# tinyclock.net
KiCad netlist of a schematic drawn in EAGLE
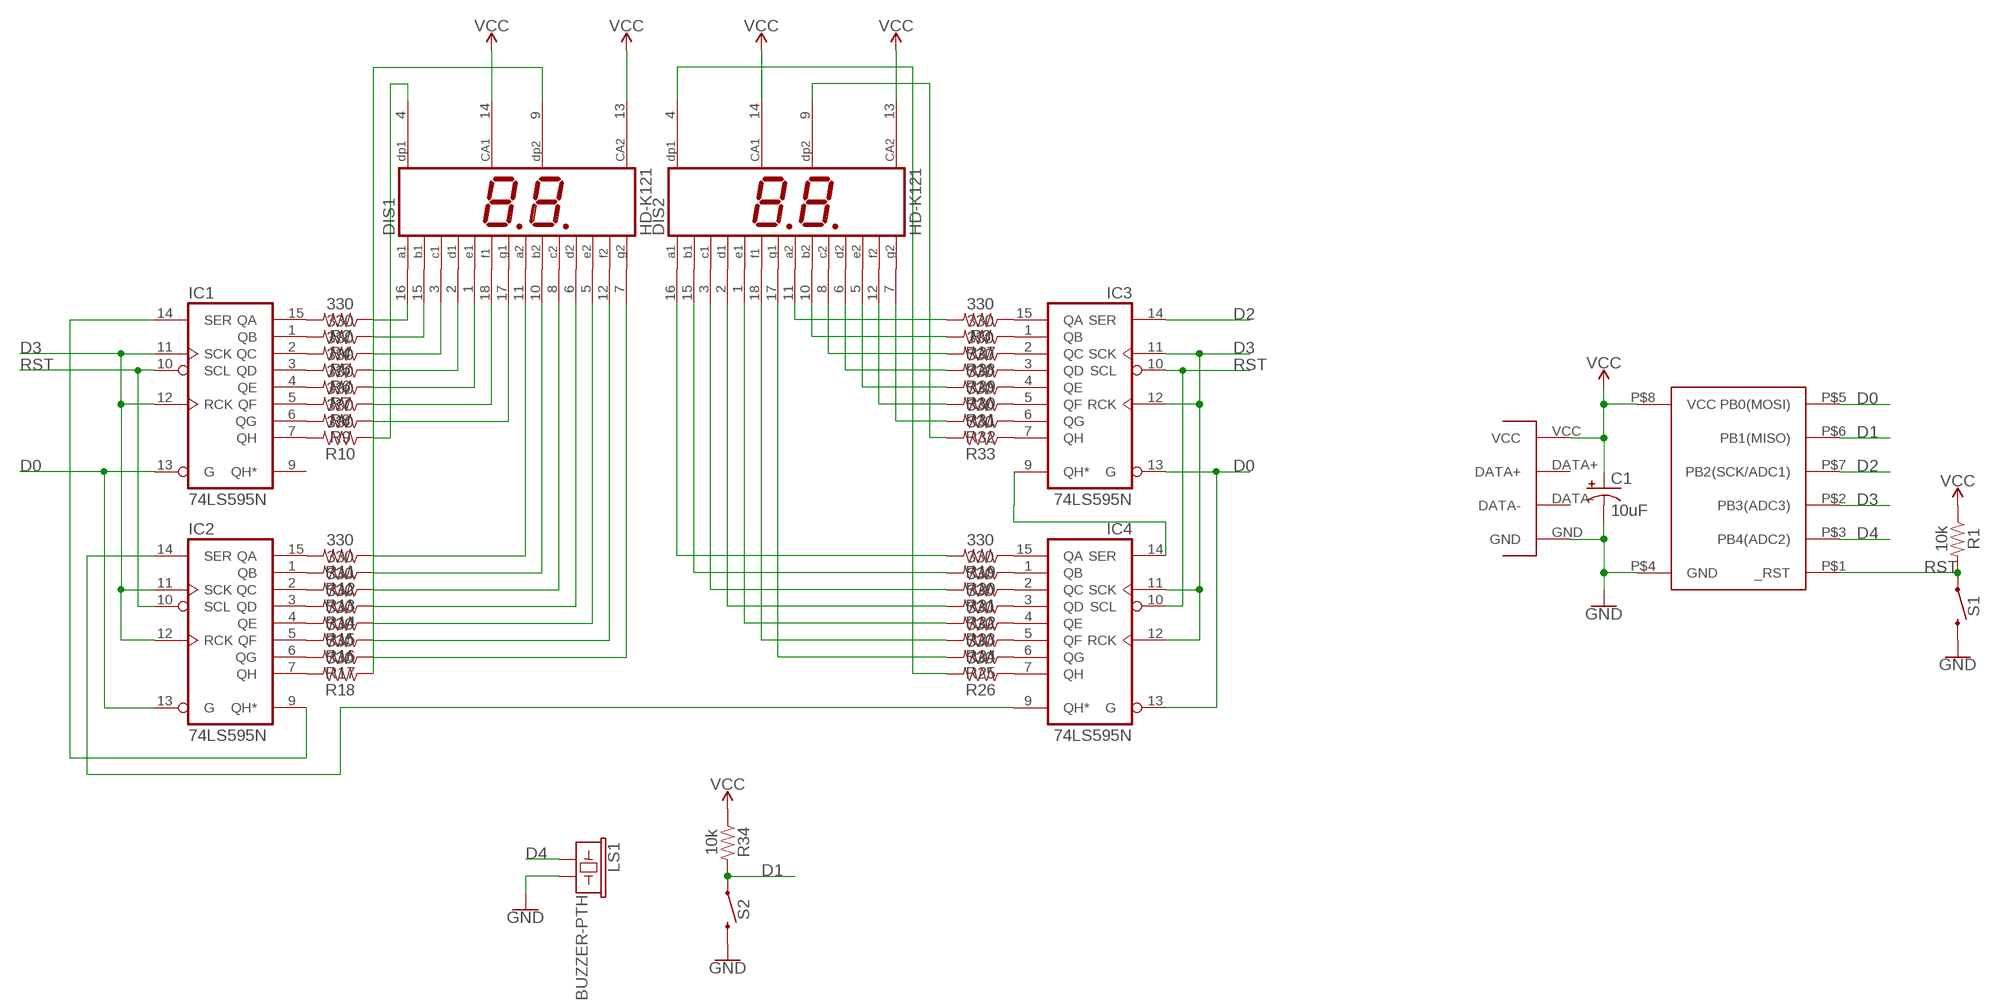
[diagram p0: schematic, sheet 1]

(export (version "E")
  (design (tool "Eeschema 10.0.6"))
  (components
    (comp (ref "C1")
      (value "10uF")
      (footprint "eagle-import:CPOL-RADIAL-5MM-10MM")
      (libsource (lib "eagle-import") (part "1000UF-RADIAL-5MM-25V-20%"))
    )
    (comp (ref "DIS1")
      (value "HD-K121")
      (footprint "eagle-import:HDSP-R")
      (libsource (lib "eagle-import") (part "HD-K121"))
    )
    (comp (ref "DIS2")
      (value "HD-K121")
      (footprint "eagle-import:HDSP-R")
      (libsource (lib "eagle-import") (part "HD-K121"))
    )
    (comp (ref "IC1")
      (value "74LS595N")
      (footprint "eagle-import:DIL16")
      (libsource (lib "eagle-import") (part "74595NLS"))
    )
    (comp (ref "IC2")
      (value "74LS595N")
      (footprint "eagle-import:DIL16")
      (libsource (lib "eagle-import") (part "74595NLS"))
    )
    (comp (ref "IC3")
      (value "74LS595N")
      (footprint "eagle-import:DIL16")
      (libsource (lib "eagle-import") (part "74595NLS"))
    )
    (comp (ref "IC4")
      (value "74LS595N")
      (footprint "eagle-import:DIL16")
      (libsource (lib "eagle-import") (part "74595NLS"))
    )
    (comp (ref "LS1")
      (value "BUZZER-PTH")
      (footprint "eagle-import:BUZZER-12MM")
      (libsource (lib "eagle-import") (part "BUZZER-PTH"))
    )
    (comp (ref "R1")
      (value "10k")
      (footprint "eagle-import:AXIAL-0.1")
      (libsource (lib "eagle-import") (part "1KOHM-VERT-1/4W-5%"))
    )
    (comp (ref "R2")
      (value "330")
      (footprint "eagle-import:AXIAL-0.1")
      (libsource (lib "eagle-import") (part "1KOHM-VERT-1/4W-5%"))
    )
    (comp (ref "R3")
      (value "330")
      (footprint "eagle-import:AXIAL-0.1")
      (libsource (lib "eagle-import") (part "1KOHM-VERT-1/4W-5%"))
    )
    (comp (ref "R4")
      (value "330")
      (footprint "eagle-import:AXIAL-0.1")
      (libsource (lib "eagle-import") (part "1KOHM-VERT-1/4W-5%"))
    )
    (comp (ref "R5")
      (value "330")
      (footprint "eagle-import:AXIAL-0.1")
      (libsource (lib "eagle-import") (part "1KOHM-VERT-1/4W-5%"))
    )
    (comp (ref "R6")
      (value "330")
      (footprint "eagle-import:AXIAL-0.1")
      (libsource (lib "eagle-import") (part "1KOHM-VERT-1/4W-5%"))
    )
    (comp (ref "R7")
      (value "330")
      (footprint "eagle-import:AXIAL-0.1")
      (libsource (lib "eagle-import") (part "1KOHM-VERT-1/4W-5%"))
    )
    (comp (ref "R8")
      (value "330")
      (footprint "eagle-import:AXIAL-0.1")
      (libsource (lib "eagle-import") (part "1KOHM-VERT-1/4W-5%"))
    )
    (comp (ref "R9")
      (value "330")
      (footprint "eagle-import:AXIAL-0.1")
      (libsource (lib "eagle-import") (part "1KOHM-VERT-1/4W-5%"))
    )
    (comp (ref "R10")
      (value "330")
      (footprint "eagle-import:AXIAL-0.1")
      (libsource (lib "eagle-import") (part "1KOHM-VERT-1/4W-5%"))
    )
    (comp (ref "R11")
      (value "330")
      (footprint "eagle-import:AXIAL-0.1")
      (libsource (lib "eagle-import") (part "1KOHM-VERT-1/4W-5%"))
    )
    (comp (ref "R12")
      (value "330")
      (footprint "eagle-import:AXIAL-0.1")
      (libsource (lib "eagle-import") (part "1KOHM-VERT-1/4W-5%"))
    )
    (comp (ref "R13")
      (value "330")
      (footprint "eagle-import:AXIAL-0.1")
      (libsource (lib "eagle-import") (part "1KOHM-VERT-1/4W-5%"))
    )
    (comp (ref "R14")
      (value "330")
      (footprint "eagle-import:AXIAL-0.1")
      (libsource (lib "eagle-import") (part "1KOHM-VERT-1/4W-5%"))
    )
    (comp (ref "R15")
      (value "330")
      (footprint "eagle-import:AXIAL-0.1")
      (libsource (lib "eagle-import") (part "1KOHM-VERT-1/4W-5%"))
    )
    (comp (ref "R16")
      (value "330")
      (footprint "eagle-import:AXIAL-0.1")
      (libsource (lib "eagle-import") (part "1KOHM-VERT-1/4W-5%"))
    )
    (comp (ref "R17")
      (value "330")
      (footprint "eagle-import:AXIAL-0.1")
      (libsource (lib "eagle-import") (part "1KOHM-VERT-1/4W-5%"))
    )
    (comp (ref "R18")
      (value "330")
      (footprint "eagle-import:AXIAL-0.1")
      (libsource (lib "eagle-import") (part "1KOHM-VERT-1/4W-5%"))
    )
    (comp (ref "R19")
      (value "330")
      (footprint "eagle-import:AXIAL-0.1")
      (libsource (lib "eagle-import") (part "1KOHM-VERT-1/4W-5%"))
    )
    (comp (ref "R20")
      (value "330")
      (footprint "eagle-import:AXIAL-0.1")
      (libsource (lib "eagle-import") (part "1KOHM-VERT-1/4W-5%"))
    )
    (comp (ref "R21")
      (value "330")
      (footprint "eagle-import:AXIAL-0.1")
      (libsource (lib "eagle-import") (part "1KOHM-VERT-1/4W-5%"))
    )
    (comp (ref "R22")
      (value "330")
      (footprint "eagle-import:AXIAL-0.1")
      (libsource (lib "eagle-import") (part "1KOHM-VERT-1/4W-5%"))
    )
    (comp (ref "R23")
      (value "330")
      (footprint "eagle-import:AXIAL-0.1")
      (libsource (lib "eagle-import") (part "1KOHM-VERT-1/4W-5%"))
    )
    (comp (ref "R24")
      (value "330")
      (footprint "eagle-import:AXIAL-0.1")
      (libsource (lib "eagle-import") (part "1KOHM-VERT-1/4W-5%"))
    )
    (comp (ref "R25")
      (value "330")
      (footprint "eagle-import:AXIAL-0.1")
      (libsource (lib "eagle-import") (part "1KOHM-VERT-1/4W-5%"))
    )
    (comp (ref "R26")
      (value "330")
      (footprint "eagle-import:AXIAL-0.1")
      (libsource (lib "eagle-import") (part "1KOHM-VERT-1/4W-5%"))
    )
    (comp (ref "R27")
      (value "330")
      (footprint "eagle-import:AXIAL-0.1")
      (libsource (lib "eagle-import") (part "1KOHM-VERT-1/4W-5%"))
    )
    (comp (ref "R28")
      (value "330")
      (footprint "eagle-import:AXIAL-0.1")
      (libsource (lib "eagle-import") (part "1KOHM-VERT-1/4W-5%"))
    )
    (comp (ref "R29")
      (value "330")
      (footprint "eagle-import:AXIAL-0.1")
      (libsource (lib "eagle-import") (part "1KOHM-VERT-1/4W-5%"))
    )
    (comp (ref "R30")
      (value "330")
      (footprint "eagle-import:AXIAL-0.1")
      (libsource (lib "eagle-import") (part "1KOHM-VERT-1/4W-5%"))
    )
    (comp (ref "R31")
      (value "330")
      (footprint "eagle-import:AXIAL-0.1")
      (libsource (lib "eagle-import") (part "1KOHM-VERT-1/4W-5%"))
    )
    (comp (ref "R32")
      (value "330")
      (footprint "eagle-import:AXIAL-0.1")
      (libsource (lib "eagle-import") (part "1KOHM-VERT-1/4W-5%"))
    )
    (comp (ref "R33")
      (value "330")
      (footprint "eagle-import:AXIAL-0.1")
      (libsource (lib "eagle-import") (part "1KOHM-VERT-1/4W-5%"))
    )
    (comp (ref "R34")
      (value "10k")
      (footprint "eagle-import:AXIAL-0.1")
      (libsource (lib "eagle-import") (part "1KOHM-VERT-1/4W-5%"))
    )
    (comp (ref "S1")
      (value "MOMENTARY-SWITCH-SPST-PTH-6.0MM")
      (footprint "eagle-import:TACTILE_SWITCH_PTH_6.0MM")
      (libsource (lib "eagle-import") (part "MOMENTARY-SWITCH-SPST-PTH-6.0MM"))
    )
    (comp (ref "S2")
      (value "MOMENTARY-SWITCH-SPST-PTH-6.0MM")
      (footprint "eagle-import:TACTILE_SWITCH_PTH_6.0MM")
      (libsource (lib "eagle-import") (part "MOMENTARY-SWITCH-SPST-PTH-6.0MM"))
    )
    (comp (ref "U$1")
      (value "ATTINY85-DIP8")
      (footprint "eagle-import:DIP8")
      (libsource (lib "eagle-import") (part "ATTINY85-DIP8"))
    )
    (comp (ref "U$2")
      (value "USBPCB")
      (footprint "eagle-import:USBPCB")
      (libsource (lib "eagle-import") (part "USBPCB"))
    )
  )
  (nets
    (net (code "1") (name "/D0") (class "Default")
      (node (ref "IC1") (pin "13") (pinfunction "G_13") (pintype "input"))
      (node (ref "IC2") (pin "13") (pinfunction "G_13") (pintype "input"))
      (node (ref "IC3") (pin "13") (pinfunction "G_13") (pintype "input"))
      (node (ref "IC4") (pin "13") (pinfunction "G_13") (pintype "input"))
      (node (ref "U$1") (pin "P$5") (pinfunction "PB0(MOSI)_P$5") (pintype "bidirectional"))
    )
    (net (code "2") (name "/D1") (class "Default")
      (node (ref "R34") (pin "P$2") (pinfunction "2_P$2") (pintype "passive"))
      (node (ref "S2") (pin "1") (pinfunction "1_1") (pintype "passive"))
      (node (ref "U$1") (pin "P$6") (pinfunction "PB1(MISO)_P$6") (pintype "bidirectional"))
    )
    (net (code "3") (name "/D2") (class "Default")
      (node (ref "IC3") (pin "14") (pinfunction "SER_14") (pintype "input"))
      (node (ref "U$1") (pin "P$7") (pinfunction "PB2(SCK/ADC1)_P$7") (pintype "bidirectional"))
    )
    (net (code "4") (name "/D3") (class "Default")
      (node (ref "IC1") (pin "11") (pinfunction "SCK_11") (pintype "input"))
      (node (ref "IC1") (pin "12") (pinfunction "RCK_12") (pintype "input"))
      (node (ref "IC2") (pin "11") (pinfunction "SCK_11") (pintype "input"))
      (node (ref "IC2") (pin "12") (pinfunction "RCK_12") (pintype "input"))
      (node (ref "IC3") (pin "11") (pinfunction "SCK_11") (pintype "input"))
      (node (ref "IC3") (pin "12") (pinfunction "RCK_12") (pintype "input"))
      (node (ref "IC4") (pin "11") (pinfunction "SCK_11") (pintype "input"))
      (node (ref "IC4") (pin "12") (pinfunction "RCK_12") (pintype "input"))
      (node (ref "U$1") (pin "P$2") (pinfunction "PB3(ADC3)_P$2") (pintype "bidirectional"))
    )
    (net (code "5") (name "/D4") (class "Default")
      (node (ref "LS1") (pin "+") (pinfunction "1_+") (pintype "passive"))
      (node (ref "U$1") (pin "P$3") (pinfunction "PB4(ADC2)_P$3") (pintype "bidirectional"))
    )
    (net (code "6") (name "/RST") (class "Default")
      (node (ref "IC1") (pin "10") (pinfunction "SCL_10") (pintype "input"))
      (node (ref "IC2") (pin "10") (pinfunction "SCL_10") (pintype "input"))
      (node (ref "IC3") (pin "10") (pinfunction "SCL_10") (pintype "input"))
      (node (ref "IC4") (pin "10") (pinfunction "SCL_10") (pintype "input"))
      (node (ref "R1") (pin "P$2") (pinfunction "2_P$2") (pintype "passive"))
      (node (ref "S1") (pin "1") (pinfunction "1_1") (pintype "passive"))
      (node (ref "U$1") (pin "P$1") (pinfunction "_RST_P$1") (pintype "bidirectional"))
    )
    (net (code "7") (name "GND") (class "Default")
      (node (ref "C1") (pin "-") (pinfunction "-_-") (pintype "passive"))
      (node (ref "LS1") (pin "-") (pinfunction "2_-") (pintype "passive"))
      (node (ref "S1") (pin "3") (pinfunction "2_3") (pintype "passive"))
      (node (ref "S2") (pin "3") (pinfunction "2_3") (pintype "passive"))
      (node (ref "U$1") (pin "P$4") (pinfunction "GND_P$4") (pintype "bidirectional"))
      (node (ref "U$2") (pin "GND") (pinfunction "GND_GND") (pintype "bidirectional"))
    )
    (net (code "8") (name "Net-(DIS1-A1)") (class "Default")
      (node (ref "DIS1") (pin "16") (pinfunction "A1_16") (pintype "passive"))
      (node (ref "R2") (pin "P$1") (pinfunction "1_P$1") (pintype "passive"))
    )
    (net (code "9") (name "Net-(DIS1-A2)") (class "Default")
      (node (ref "DIS1") (pin "11") (pinfunction "A2_11") (pintype "passive"))
      (node (ref "R11") (pin "P$1") (pinfunction "1_P$1") (pintype "passive"))
    )
    (net (code "10") (name "Net-(DIS1-B1)") (class "Default")
      (node (ref "DIS1") (pin "15") (pinfunction "B1_15") (pintype "passive"))
      (node (ref "R4") (pin "P$1") (pinfunction "1_P$1") (pintype "passive"))
    )
    (net (code "11") (name "Net-(DIS1-B2)") (class "Default")
      (node (ref "DIS1") (pin "10") (pinfunction "B2_10") (pintype "passive"))
      (node (ref "R12") (pin "P$1") (pinfunction "1_P$1") (pintype "passive"))
    )
    (net (code "12") (name "Net-(DIS1-C1)") (class "Default")
      (node (ref "DIS1") (pin "3") (pinfunction "C1_3") (pintype "passive"))
      (node (ref "R5") (pin "P$1") (pinfunction "1_P$1") (pintype "passive"))
    )
    (net (code "13") (name "Net-(DIS1-C2)") (class "Default")
      (node (ref "DIS1") (pin "8") (pinfunction "C2_8") (pintype "passive"))
      (node (ref "R13") (pin "P$1") (pinfunction "1_P$1") (pintype "passive"))
    )
    (net (code "14") (name "Net-(DIS1-D1)") (class "Default")
      (node (ref "DIS1") (pin "2") (pinfunction "D1_2") (pintype "passive"))
      (node (ref "R6") (pin "P$1") (pinfunction "1_P$1") (pintype "passive"))
    )
    (net (code "15") (name "Net-(DIS1-D2)") (class "Default")
      (node (ref "DIS1") (pin "6") (pinfunction "D2_6") (pintype "passive"))
      (node (ref "R14") (pin "P$1") (pinfunction "1_P$1") (pintype "passive"))
    )
    (net (code "16") (name "Net-(DIS1-DP1)") (class "Default")
      (node (ref "DIS1") (pin "4") (pinfunction "DP1_4") (pintype "passive"))
      (node (ref "R10") (pin "P$1") (pinfunction "1_P$1") (pintype "passive"))
    )
    (net (code "17") (name "Net-(DIS1-DP2)") (class "Default")
      (node (ref "DIS1") (pin "9") (pinfunction "DP2_9") (pintype "passive"))
      (node (ref "R18") (pin "P$1") (pinfunction "1_P$1") (pintype "passive"))
    )
    (net (code "18") (name "Net-(DIS1-E1)") (class "Default")
      (node (ref "DIS1") (pin "1") (pinfunction "E1_1") (pintype "passive"))
      (node (ref "R7") (pin "P$1") (pinfunction "1_P$1") (pintype "passive"))
    )
    (net (code "19") (name "Net-(DIS1-E2)") (class "Default")
      (node (ref "DIS1") (pin "5") (pinfunction "E2_5") (pintype "passive"))
      (node (ref "R15") (pin "P$1") (pinfunction "1_P$1") (pintype "passive"))
    )
    (net (code "20") (name "Net-(DIS1-F1)") (class "Default")
      (node (ref "DIS1") (pin "18") (pinfunction "F1_18") (pintype "passive"))
      (node (ref "R8") (pin "P$1") (pinfunction "1_P$1") (pintype "passive"))
    )
    (net (code "21") (name "Net-(DIS1-F2)") (class "Default")
      (node (ref "DIS1") (pin "12") (pinfunction "F2_12") (pintype "passive"))
      (node (ref "R16") (pin "P$1") (pinfunction "1_P$1") (pintype "passive"))
    )
    (net (code "22") (name "Net-(DIS1-G1)") (class "Default")
      (node (ref "DIS1") (pin "17") (pinfunction "G1_17") (pintype "passive"))
      (node (ref "R9") (pin "P$1") (pinfunction "1_P$1") (pintype "passive"))
    )
    (net (code "23") (name "Net-(DIS1-G2)") (class "Default")
      (node (ref "DIS1") (pin "7") (pinfunction "G2_7") (pintype "passive"))
      (node (ref "R17") (pin "P$1") (pinfunction "1_P$1") (pintype "passive"))
    )
    (net (code "24") (name "Net-(DIS2-A1)") (class "Default")
      (node (ref "DIS2") (pin "16") (pinfunction "A1_16") (pintype "passive"))
      (node (ref "R19") (pin "P$2") (pinfunction "2_P$2") (pintype "passive"))
    )
    (net (code "25") (name "Net-(DIS2-A2)") (class "Default")
      (node (ref "DIS2") (pin "11") (pinfunction "A2_11") (pintype "passive"))
      (node (ref "R3") (pin "P$2") (pinfunction "2_P$2") (pintype "passive"))
    )
    (net (code "26") (name "Net-(DIS2-B1)") (class "Default")
      (node (ref "DIS2") (pin "15") (pinfunction "B1_15") (pintype "passive"))
      (node (ref "R20") (pin "P$2") (pinfunction "2_P$2") (pintype "passive"))
    )
    (net (code "27") (name "Net-(DIS2-B2)") (class "Default")
      (node (ref "DIS2") (pin "10") (pinfunction "B2_10") (pintype "passive"))
      (node (ref "R27") (pin "P$2") (pinfunction "2_P$2") (pintype "passive"))
    )
    (net (code "28") (name "Net-(DIS2-C1)") (class "Default")
      (node (ref "DIS2") (pin "3") (pinfunction "C1_3") (pintype "passive"))
      (node (ref "R21") (pin "P$2") (pinfunction "2_P$2") (pintype "passive"))
    )
    (net (code "29") (name "Net-(DIS2-C2)") (class "Default")
      (node (ref "DIS2") (pin "8") (pinfunction "C2_8") (pintype "passive"))
      (node (ref "R28") (pin "P$2") (pinfunction "2_P$2") (pintype "passive"))
    )
    (net (code "30") (name "Net-(DIS2-D1)") (class "Default")
      (node (ref "DIS2") (pin "2") (pinfunction "D1_2") (pintype "passive"))
      (node (ref "R22") (pin "P$2") (pinfunction "2_P$2") (pintype "passive"))
    )
    (net (code "31") (name "Net-(DIS2-D2)") (class "Default")
      (node (ref "DIS2") (pin "6") (pinfunction "D2_6") (pintype "passive"))
      (node (ref "R29") (pin "P$2") (pinfunction "2_P$2") (pintype "passive"))
    )
    (net (code "32") (name "Net-(DIS2-DP1)") (class "Default")
      (node (ref "DIS2") (pin "4") (pinfunction "DP1_4") (pintype "passive"))
      (node (ref "R26") (pin "P$2") (pinfunction "2_P$2") (pintype "passive"))
    )
    (net (code "33") (name "Net-(DIS2-DP2)") (class "Default")
      (node (ref "DIS2") (pin "9") (pinfunction "DP2_9") (pintype "passive"))
      (node (ref "R33") (pin "P$2") (pinfunction "2_P$2") (pintype "passive"))
    )
    (net (code "34") (name "Net-(DIS2-E1)") (class "Default")
      (node (ref "DIS2") (pin "1") (pinfunction "E1_1") (pintype "passive"))
      (node (ref "R23") (pin "P$2") (pinfunction "2_P$2") (pintype "passive"))
    )
    (net (code "35") (name "Net-(DIS2-E2)") (class "Default")
      (node (ref "DIS2") (pin "5") (pinfunction "E2_5") (pintype "passive"))
      (node (ref "R30") (pin "P$2") (pinfunction "2_P$2") (pintype "passive"))
    )
    (net (code "36") (name "Net-(DIS2-F1)") (class "Default")
      (node (ref "DIS2") (pin "18") (pinfunction "F1_18") (pintype "passive"))
      (node (ref "R24") (pin "P$2") (pinfunction "2_P$2") (pintype "passive"))
    )
    (net (code "37") (name "Net-(DIS2-F2)") (class "Default")
      (node (ref "DIS2") (pin "12") (pinfunction "F2_12") (pintype "passive"))
      (node (ref "R31") (pin "P$2") (pinfunction "2_P$2") (pintype "passive"))
    )
    (net (code "38") (name "Net-(DIS2-G1)") (class "Default")
      (node (ref "DIS2") (pin "17") (pinfunction "G1_17") (pintype "passive"))
      (node (ref "R25") (pin "P$2") (pinfunction "2_P$2") (pintype "passive"))
    )
    (net (code "39") (name "Net-(DIS2-G2)") (class "Default")
      (node (ref "DIS2") (pin "7") (pinfunction "G2_7") (pintype "passive"))
      (node (ref "R32") (pin "P$2") (pinfunction "2_P$2") (pintype "passive"))
    )
    (net (code "40") (name "Net-(IC1A-QA)") (class "Default")
      (node (ref "IC1") (pin "15") (pinfunction "QA_15") (pintype "tri_state"))
      (node (ref "R2") (pin "P$2") (pinfunction "2_P$2") (pintype "passive"))
    )
    (net (code "41") (name "Net-(IC1A-QB)") (class "Default")
      (node (ref "IC1") (pin "1") (pinfunction "QB_1") (pintype "tri_state"))
      (node (ref "R4") (pin "P$2") (pinfunction "2_P$2") (pintype "passive"))
    )
    (net (code "42") (name "Net-(IC1A-QC)") (class "Default")
      (node (ref "IC1") (pin "2") (pinfunction "QC_2") (pintype "tri_state"))
      (node (ref "R5") (pin "P$2") (pinfunction "2_P$2") (pintype "passive"))
    )
    (net (code "43") (name "Net-(IC1A-QD)") (class "Default")
      (node (ref "IC1") (pin "3") (pinfunction "QD_3") (pintype "tri_state"))
      (node (ref "R6") (pin "P$2") (pinfunction "2_P$2") (pintype "passive"))
    )
    (net (code "44") (name "Net-(IC1A-QE)") (class "Default")
      (node (ref "IC1") (pin "4") (pinfunction "QE_4") (pintype "tri_state"))
      (node (ref "R7") (pin "P$2") (pinfunction "2_P$2") (pintype "passive"))
    )
    (net (code "45") (name "Net-(IC1A-QF)") (class "Default")
      (node (ref "IC1") (pin "5") (pinfunction "QF_5") (pintype "tri_state"))
      (node (ref "R8") (pin "P$2") (pinfunction "2_P$2") (pintype "passive"))
    )
    (net (code "46") (name "Net-(IC1A-QG)") (class "Default")
      (node (ref "IC1") (pin "6") (pinfunction "QG_6") (pintype "tri_state"))
      (node (ref "R9") (pin "P$2") (pinfunction "2_P$2") (pintype "passive"))
    )
    (net (code "47") (name "Net-(IC1A-QH)") (class "Default")
      (node (ref "IC1") (pin "7") (pinfunction "QH_7") (pintype "tri_state"))
      (node (ref "R10") (pin "P$2") (pinfunction "2_P$2") (pintype "passive"))
    )
    (net (code "48") (name "Net-(IC1A-SER)") (class "Default")
      (node (ref "IC1") (pin "14") (pinfunction "SER_14") (pintype "input"))
      (node (ref "IC2") (pin "9") (pinfunction "QH*_9") (pintype "tri_state"))
    )
    (net (code "49") (name "Net-(IC2A-QA)") (class "Default")
      (node (ref "IC2") (pin "15") (pinfunction "QA_15") (pintype "tri_state"))
      (node (ref "R11") (pin "P$2") (pinfunction "2_P$2") (pintype "passive"))
    )
    (net (code "50") (name "Net-(IC2A-QB)") (class "Default")
      (node (ref "IC2") (pin "1") (pinfunction "QB_1") (pintype "tri_state"))
      (node (ref "R12") (pin "P$2") (pinfunction "2_P$2") (pintype "passive"))
    )
    (net (code "51") (name "Net-(IC2A-QC)") (class "Default")
      (node (ref "IC2") (pin "2") (pinfunction "QC_2") (pintype "tri_state"))
      (node (ref "R13") (pin "P$2") (pinfunction "2_P$2") (pintype "passive"))
    )
    (net (code "52") (name "Net-(IC2A-QD)") (class "Default")
      (node (ref "IC2") (pin "3") (pinfunction "QD_3") (pintype "tri_state"))
      (node (ref "R14") (pin "P$2") (pinfunction "2_P$2") (pintype "passive"))
    )
    (net (code "53") (name "Net-(IC2A-QE)") (class "Default")
      (node (ref "IC2") (pin "4") (pinfunction "QE_4") (pintype "tri_state"))
      (node (ref "R15") (pin "P$2") (pinfunction "2_P$2") (pintype "passive"))
    )
    (net (code "54") (name "Net-(IC2A-QF)") (class "Default")
      (node (ref "IC2") (pin "5") (pinfunction "QF_5") (pintype "tri_state"))
      (node (ref "R16") (pin "P$2") (pinfunction "2_P$2") (pintype "passive"))
    )
    (net (code "55") (name "Net-(IC2A-QG)") (class "Default")
      (node (ref "IC2") (pin "6") (pinfunction "QG_6") (pintype "tri_state"))
      (node (ref "R17") (pin "P$2") (pinfunction "2_P$2") (pintype "passive"))
    )
    (net (code "56") (name "Net-(IC2A-QH)") (class "Default")
      (node (ref "IC2") (pin "7") (pinfunction "QH_7") (pintype "tri_state"))
      (node (ref "R18") (pin "P$2") (pinfunction "2_P$2") (pintype "passive"))
    )
    (net (code "57") (name "Net-(IC2A-SER)") (class "Default")
      (node (ref "IC2") (pin "14") (pinfunction "SER_14") (pintype "input"))
      (node (ref "IC4") (pin "9") (pinfunction "QH*_9") (pintype "tri_state"))
    )
    (net (code "58") (name "Net-(IC3A-QA)") (class "Default")
      (node (ref "IC3") (pin "15") (pinfunction "QA_15") (pintype "tri_state"))
      (node (ref "R3") (pin "P$1") (pinfunction "1_P$1") (pintype "passive"))
    )
    (net (code "59") (name "Net-(IC3A-QB)") (class "Default")
      (node (ref "IC3") (pin "1") (pinfunction "QB_1") (pintype "tri_state"))
      (node (ref "R27") (pin "P$1") (pinfunction "1_P$1") (pintype "passive"))
    )
    (net (code "60") (name "Net-(IC3A-QC)") (class "Default")
      (node (ref "IC3") (pin "2") (pinfunction "QC_2") (pintype "tri_state"))
      (node (ref "R28") (pin "P$1") (pinfunction "1_P$1") (pintype "passive"))
    )
    (net (code "61") (name "Net-(IC3A-QD)") (class "Default")
      (node (ref "IC3") (pin "3") (pinfunction "QD_3") (pintype "tri_state"))
      (node (ref "R29") (pin "P$1") (pinfunction "1_P$1") (pintype "passive"))
    )
    (net (code "62") (name "Net-(IC3A-QE)") (class "Default")
      (node (ref "IC3") (pin "4") (pinfunction "QE_4") (pintype "tri_state"))
      (node (ref "R30") (pin "P$1") (pinfunction "1_P$1") (pintype "passive"))
    )
    (net (code "63") (name "Net-(IC3A-QF)") (class "Default")
      (node (ref "IC3") (pin "5") (pinfunction "QF_5") (pintype "tri_state"))
      (node (ref "R31") (pin "P$1") (pinfunction "1_P$1") (pintype "passive"))
    )
    (net (code "64") (name "Net-(IC3A-QG)") (class "Default")
      (node (ref "IC3") (pin "6") (pinfunction "QG_6") (pintype "tri_state"))
      (node (ref "R32") (pin "P$1") (pinfunction "1_P$1") (pintype "passive"))
    )
    (net (code "65") (name "Net-(IC3A-QH)") (class "Default")
      (node (ref "IC3") (pin "7") (pinfunction "QH_7") (pintype "tri_state"))
      (node (ref "R33") (pin "P$1") (pinfunction "1_P$1") (pintype "passive"))
    )
    (net (code "66") (name "Net-(IC3A-QH*)") (class "Default")
      (node (ref "IC3") (pin "9") (pinfunction "QH*_9") (pintype "tri_state"))
      (node (ref "IC4") (pin "14") (pinfunction "SER_14") (pintype "input"))
    )
    (net (code "67") (name "Net-(IC4A-QA)") (class "Default")
      (node (ref "IC4") (pin "15") (pinfunction "QA_15") (pintype "tri_state"))
      (node (ref "R19") (pin "P$1") (pinfunction "1_P$1") (pintype "passive"))
    )
    (net (code "68") (name "Net-(IC4A-QB)") (class "Default")
      (node (ref "IC4") (pin "1") (pinfunction "QB_1") (pintype "tri_state"))
      (node (ref "R20") (pin "P$1") (pinfunction "1_P$1") (pintype "passive"))
    )
    (net (code "69") (name "Net-(IC4A-QC)") (class "Default")
      (node (ref "IC4") (pin "2") (pinfunction "QC_2") (pintype "tri_state"))
      (node (ref "R21") (pin "P$1") (pinfunction "1_P$1") (pintype "passive"))
    )
    (net (code "70") (name "Net-(IC4A-QD)") (class "Default")
      (node (ref "IC4") (pin "3") (pinfunction "QD_3") (pintype "tri_state"))
      (node (ref "R22") (pin "P$1") (pinfunction "1_P$1") (pintype "passive"))
    )
    (net (code "71") (name "Net-(IC4A-QE)") (class "Default")
      (node (ref "IC4") (pin "4") (pinfunction "QE_4") (pintype "tri_state"))
      (node (ref "R23") (pin "P$1") (pinfunction "1_P$1") (pintype "passive"))
    )
    (net (code "72") (name "Net-(IC4A-QF)") (class "Default")
      (node (ref "IC4") (pin "5") (pinfunction "QF_5") (pintype "tri_state"))
      (node (ref "R24") (pin "P$1") (pinfunction "1_P$1") (pintype "passive"))
    )
    (net (code "73") (name "Net-(IC4A-QG)") (class "Default")
      (node (ref "IC4") (pin "6") (pinfunction "QG_6") (pintype "tri_state"))
      (node (ref "R25") (pin "P$1") (pinfunction "1_P$1") (pintype "passive"))
    )
    (net (code "74") (name "Net-(IC4A-QH)") (class "Default")
      (node (ref "IC4") (pin "7") (pinfunction "QH_7") (pintype "tri_state"))
      (node (ref "R26") (pin "P$1") (pinfunction "1_P$1") (pintype "passive"))
    )
    (net (code "75") (name "VCC") (class "Default")
      (node (ref "C1") (pin "+") (pinfunction "+_+") (pintype "passive"))
      (node (ref "DIS1") (pin "13") (pinfunction "CA2_13") (pintype "passive"))
      (node (ref "DIS1") (pin "14") (pinfunction "CA1_14") (pintype "passive"))
      (node (ref "DIS2") (pin "13") (pinfunction "CA2_13") (pintype "passive"))
      (node (ref "DIS2") (pin "14") (pinfunction "CA1_14") (pintype "passive"))
      (node (ref "R1") (pin "P$1") (pinfunction "1_P$1") (pintype "passive"))
      (node (ref "R34") (pin "P$1") (pinfunction "1_P$1") (pintype "passive"))
      (node (ref "U$1") (pin "P$8") (pinfunction "VCC_P$8") (pintype "bidirectional"))
      (node (ref "U$2") (pin "VCC") (pinfunction "VCC_VCC") (pintype "bidirectional"))
    )
    (net (code "76") (name "unconnected-(IC1A-QH*-Pad9)") (class "Default")
      (node (ref "IC1") (pin "9") (pinfunction "QH*_9") (pintype "tri_state"))
    )
    (net (code "77") (name "unconnected-(U$2-PadDATA+)") (class "Default")
      (node (ref "U$2") (pin "DATA+") (pinfunction "DATA+_DATA+") (pintype "bidirectional"))
    )
    (net (code "78") (name "unconnected-(U$2-PadDATA-)") (class "Default")
      (node (ref "U$2") (pin "DATA-") (pinfunction "DATA-_DATA-") (pintype "bidirectional"))
    )
  )
)
